# SAS_Connectors.net
KiCad netlist of a schematic drawn in Altium Designer
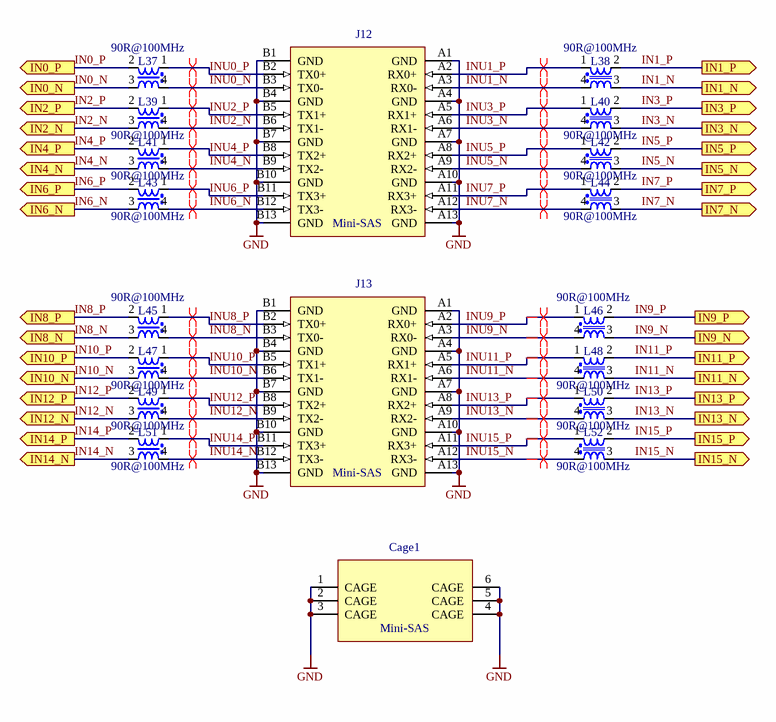
[diagram p0: SAS_Connectors.SchDoc]

(export (version "E")
  (design (tool "Eeschema 10.0.6"))
  (components
    (comp (ref "Cage1")
      (value "Mini-SAS")
      (footprint "TYCO_1888321-2")
      (description "Mini-SAS Cage (6Pins)")
      (fields
        (field (name "PART NUMBER") "TYCO_1888321-2")
        (field (name "MANUFACTURER") "TYCO ELECTRONICS")
        (field (name "AUTHOR") "CERN DEM BC")
      )
      (libsource (lib "Connectors") (part "Mini-SAS Cage (6Pins)"))
    )
    (comp (ref "J12")
      (value "Mini-SAS")
      (footprint "TYCO_1761987-7")
      (description "26 Position Mini-Sas Connector (Quad Small Form-Factor SFF-8088)")
      (fields
        (field (name "PART NUMBER") "TYCO_1761987-7")
        (field (name "MANUFACTURER") "TYCO ELECTRONICS")
        (field (name "AUTHOR") "CERN DEM MR")
      )
      (libsource (lib "Connectors") (part "Mini-SAS"))
    )
    (comp (ref "J13")
      (value "Mini-SAS")
      (footprint "TYCO_1761987-7")
      (description "26 Position Mini-Sas Connector (Quad Small Form-Factor SFF-8088)")
      (fields
        (field (name "PART NUMBER") "TYCO_1761987-7")
        (field (name "MANUFACTURER") "TYCO ELECTRONICS")
        (field (name "AUTHOR") "CERN DEM MR")
      )
      (libsource (lib "Connectors") (part "Mini-SAS"))
    )
    (comp (ref "L37")
      (value "90R@100MHz")
      (footprint "IND_MURATA_DLW21S")
      (description "Inductor Common Mode")
      (fields
        (field (name "PART NUMBER") "IND_MURATA_DLW21SN900SQ2L")
        (field (name "POWER") "330mA")
        (field (name "AUTHOR") "CERN DEM JLC")
      )
      (libsource (lib "Inductors & Transformers") (part "Inductor Common Mode 1Dot-2 4Dot-3"))
    )
    (comp (ref "L38")
      (value "90R@100MHz")
      (footprint "IND_MURATA_DLW21S")
      (description "Inductor Common Mode")
      (fields
        (field (name "PART NUMBER") "IND_MURATA_DLW21SN900SQ2L")
        (field (name "POWER") "330mA")
        (field (name "AUTHOR") "CERN DEM JLC")
      )
      (libsource (lib "") (part "Inductor Common Mode 1Dot-2 4Dot-3_1"))
    )
    (comp (ref "L39")
      (value "90R@100MHz")
      (footprint "IND_MURATA_DLW21S")
      (description "Inductor Common Mode")
      (fields
        (field (name "PART NUMBER") "IND_MURATA_DLW21SN900SQ2L")
        (field (name "POWER") "330mA")
        (field (name "AUTHOR") "CERN DEM JLC")
      )
      (libsource (lib "Inductors & Transformers") (part "Inductor Common Mode 1Dot-2 4Dot-3"))
    )
    (comp (ref "L40")
      (value "90R@100MHz")
      (footprint "IND_MURATA_DLW21S")
      (description "Inductor Common Mode")
      (fields
        (field (name "PART NUMBER") "IND_MURATA_DLW21SN900SQ2L")
        (field (name "POWER") "330mA")
        (field (name "AUTHOR") "CERN DEM JLC")
      )
      (libsource (lib "") (part "Inductor Common Mode 1Dot-2 4Dot-3_1"))
    )
    (comp (ref "L41")
      (value "90R@100MHz")
      (footprint "IND_MURATA_DLW21S")
      (description "Inductor Common Mode")
      (fields
        (field (name "PART NUMBER") "IND_MURATA_DLW21SN900SQ2L")
        (field (name "POWER") "330mA")
        (field (name "AUTHOR") "CERN DEM JLC")
      )
      (libsource (lib "Inductors & Transformers") (part "Inductor Common Mode 1Dot-2 4Dot-3"))
    )
    (comp (ref "L42")
      (value "90R@100MHz")
      (footprint "IND_MURATA_DLW21S")
      (description "Inductor Common Mode")
      (fields
        (field (name "PART NUMBER") "IND_MURATA_DLW21SN900SQ2L")
        (field (name "POWER") "330mA")
        (field (name "AUTHOR") "CERN DEM JLC")
      )
      (libsource (lib "") (part "Inductor Common Mode 1Dot-2 4Dot-3_1"))
    )
    (comp (ref "L43")
      (value "90R@100MHz")
      (footprint "IND_MURATA_DLW21S")
      (description "Inductor Common Mode")
      (fields
        (field (name "PART NUMBER") "IND_MURATA_DLW21SN900SQ2L")
        (field (name "POWER") "330mA")
        (field (name "AUTHOR") "CERN DEM JLC")
      )
      (libsource (lib "Inductors & Transformers") (part "Inductor Common Mode 1Dot-2 4Dot-3"))
    )
    (comp (ref "L44")
      (value "90R@100MHz")
      (footprint "IND_MURATA_DLW21S")
      (description "Inductor Common Mode")
      (fields
        (field (name "PART NUMBER") "IND_MURATA_DLW21SN900SQ2L")
        (field (name "POWER") "330mA")
        (field (name "AUTHOR") "CERN DEM JLC")
      )
      (libsource (lib "") (part "Inductor Common Mode 1Dot-2 4Dot-3_1"))
    )
    (comp (ref "L45")
      (value "90R@100MHz")
      (footprint "IND_MURATA_DLW21S")
      (description "Inductor Common Mode")
      (fields
        (field (name "PART NUMBER") "IND_MURATA_DLW21SN900SQ2L")
        (field (name "POWER") "330mA")
        (field (name "AUTHOR") "CERN DEM JLC")
      )
      (libsource (lib "Inductors & Transformers") (part "Inductor Common Mode 1Dot-2 4Dot-3"))
    )
    (comp (ref "L46")
      (value "90R@100MHz")
      (footprint "IND_MURATA_DLW21S")
      (description "Inductor Common Mode")
      (fields
        (field (name "PART NUMBER") "IND_MURATA_DLW21SN900SQ2L")
        (field (name "POWER") "330mA")
        (field (name "AUTHOR") "CERN DEM JLC")
      )
      (libsource (lib "") (part "Inductor Common Mode 1Dot-2 4Dot-3_1"))
    )
    (comp (ref "L47")
      (value "90R@100MHz")
      (footprint "IND_MURATA_DLW21S")
      (description "Inductor Common Mode")
      (fields
        (field (name "PART NUMBER") "IND_MURATA_DLW21SN900SQ2L")
        (field (name "POWER") "330mA")
        (field (name "AUTHOR") "CERN DEM JLC")
      )
      (libsource (lib "Inductors & Transformers") (part "Inductor Common Mode 1Dot-2 4Dot-3"))
    )
    (comp (ref "L48")
      (value "90R@100MHz")
      (footprint "IND_MURATA_DLW21S")
      (description "Inductor Common Mode")
      (fields
        (field (name "PART NUMBER") "IND_MURATA_DLW21SN900SQ2L")
        (field (name "POWER") "330mA")
        (field (name "AUTHOR") "CERN DEM JLC")
      )
      (libsource (lib "") (part "Inductor Common Mode 1Dot-2 4Dot-3_1"))
    )
    (comp (ref "L49")
      (value "90R@100MHz")
      (footprint "IND_MURATA_DLW21S")
      (description "Inductor Common Mode")
      (fields
        (field (name "PART NUMBER") "IND_MURATA_DLW21SN900SQ2L")
        (field (name "POWER") "330mA")
        (field (name "AUTHOR") "CERN DEM JLC")
      )
      (libsource (lib "Inductors & Transformers") (part "Inductor Common Mode 1Dot-2 4Dot-3"))
    )
    (comp (ref "L50")
      (value "90R@100MHz")
      (footprint "IND_MURATA_DLW21S")
      (description "Inductor Common Mode")
      (fields
        (field (name "PART NUMBER") "IND_MURATA_DLW21SN900SQ2L")
        (field (name "POWER") "330mA")
        (field (name "AUTHOR") "CERN DEM JLC")
      )
      (libsource (lib "") (part "Inductor Common Mode 1Dot-2 4Dot-3_1"))
    )
    (comp (ref "L51")
      (value "90R@100MHz")
      (footprint "IND_MURATA_DLW21S")
      (description "Inductor Common Mode")
      (fields
        (field (name "PART NUMBER") "IND_MURATA_DLW21SN900SQ2L")
        (field (name "POWER") "330mA")
        (field (name "AUTHOR") "CERN DEM JLC")
      )
      (libsource (lib "Inductors & Transformers") (part "Inductor Common Mode 1Dot-2 4Dot-3"))
    )
    (comp (ref "L52")
      (value "90R@100MHz")
      (footprint "IND_MURATA_DLW21S")
      (description "Inductor Common Mode")
      (fields
        (field (name "PART NUMBER") "IND_MURATA_DLW21SN900SQ2L")
        (field (name "POWER") "330mA")
        (field (name "AUTHOR") "CERN DEM JLC")
      )
      (libsource (lib "") (part "Inductor Common Mode 1Dot-2 4Dot-3_1"))
    )
  )
  (nets
    (net (code "1") (name "/IN0_N") (class "Default")
      (node (ref "L37") (pin "3") (pinfunction "3_3") (pintype "passive"))
    )
    (net (code "2") (name "/IN0_P") (class "Default")
      (node (ref "L37") (pin "2") (pinfunction "2_2") (pintype "passive"))
    )
    (net (code "3") (name "/IN1_N") (class "Default")
      (node (ref "L38") (pin "3") (pinfunction "3_3") (pintype "passive"))
    )
    (net (code "4") (name "/IN1_P") (class "Default")
      (node (ref "L38") (pin "2") (pinfunction "2_2") (pintype "passive"))
    )
    (net (code "5") (name "/IN2_N") (class "Default")
      (node (ref "L39") (pin "3") (pinfunction "3_3") (pintype "passive"))
    )
    (net (code "6") (name "/IN2_P") (class "Default")
      (node (ref "L39") (pin "2") (pinfunction "2_2") (pintype "passive"))
    )
    (net (code "7") (name "/IN3_N") (class "Default")
      (node (ref "L40") (pin "3") (pinfunction "3_3") (pintype "passive"))
    )
    (net (code "8") (name "/IN3_P") (class "Default")
      (node (ref "L40") (pin "2") (pinfunction "2_2") (pintype "passive"))
    )
    (net (code "9") (name "/IN4_N") (class "Default")
      (node (ref "L41") (pin "3") (pinfunction "3_3") (pintype "passive"))
    )
    (net (code "10") (name "/IN4_P") (class "Default")
      (node (ref "L41") (pin "2") (pinfunction "2_2") (pintype "passive"))
    )
    (net (code "11") (name "/IN5_N") (class "Default")
      (node (ref "L42") (pin "3") (pinfunction "3_3") (pintype "passive"))
    )
    (net (code "12") (name "/IN5_P") (class "Default")
      (node (ref "L42") (pin "2") (pinfunction "2_2") (pintype "passive"))
    )
    (net (code "13") (name "/IN6_N") (class "Default")
      (node (ref "L43") (pin "3") (pinfunction "3_3") (pintype "passive"))
    )
    (net (code "14") (name "/IN6_P") (class "Default")
      (node (ref "L43") (pin "2") (pinfunction "2_2") (pintype "passive"))
    )
    (net (code "15") (name "/IN7_N") (class "Default")
      (node (ref "L44") (pin "3") (pinfunction "3_3") (pintype "passive"))
    )
    (net (code "16") (name "/IN7_P") (class "Default")
      (node (ref "L44") (pin "2") (pinfunction "2_2") (pintype "passive"))
    )
    (net (code "17") (name "/IN8_N") (class "Default")
      (node (ref "L45") (pin "3") (pinfunction "3_3") (pintype "passive"))
    )
    (net (code "18") (name "/IN8_P") (class "Default")
      (node (ref "L45") (pin "2") (pinfunction "2_2") (pintype "passive"))
    )
    (net (code "19") (name "/IN9_N") (class "Default")
      (node (ref "L46") (pin "3") (pinfunction "3_3") (pintype "passive"))
    )
    (net (code "20") (name "/IN9_P") (class "Default")
      (node (ref "L46") (pin "2") (pinfunction "2_2") (pintype "passive"))
    )
    (net (code "21") (name "/IN10_N") (class "Default")
      (node (ref "L47") (pin "3") (pinfunction "3_3") (pintype "passive"))
    )
    (net (code "22") (name "/IN10_P") (class "Default")
      (node (ref "L47") (pin "2") (pinfunction "2_2") (pintype "passive"))
    )
    (net (code "23") (name "/IN11_N") (class "Default")
      (node (ref "L48") (pin "3") (pinfunction "3_3") (pintype "passive"))
    )
    (net (code "24") (name "/IN11_P") (class "Default")
      (node (ref "L48") (pin "2") (pinfunction "2_2") (pintype "passive"))
    )
    (net (code "25") (name "/IN12_N") (class "Default")
      (node (ref "L49") (pin "3") (pinfunction "3_3") (pintype "passive"))
    )
    (net (code "26") (name "/IN12_P") (class "Default")
      (node (ref "L49") (pin "2") (pinfunction "2_2") (pintype "passive"))
    )
    (net (code "27") (name "/IN13_N") (class "Default")
      (node (ref "L50") (pin "3") (pinfunction "3_3") (pintype "passive"))
    )
    (net (code "28") (name "/IN13_P") (class "Default")
      (node (ref "L50") (pin "2") (pinfunction "2_2") (pintype "passive"))
    )
    (net (code "29") (name "/IN14_N") (class "Default")
      (node (ref "L51") (pin "3") (pinfunction "3_3") (pintype "passive"))
    )
    (net (code "30") (name "/IN14_P") (class "Default")
      (node (ref "L51") (pin "2") (pinfunction "2_2") (pintype "passive"))
    )
    (net (code "31") (name "/IN15_N") (class "Default")
      (node (ref "L52") (pin "3") (pinfunction "3_3") (pintype "passive"))
    )
    (net (code "32") (name "/IN15_P") (class "Default")
      (node (ref "L52") (pin "2") (pinfunction "2_2") (pintype "passive"))
    )
    (net (code "33") (name "/INU0_N") (class "Default")
      (node (ref "J12") (pin "B3") (pinfunction "TX0-_B3") (pintype "input"))
      (node (ref "L37") (pin "4") (pinfunction "4_4") (pintype "passive"))
    )
    (net (code "34") (name "/INU0_P") (class "Default")
      (node (ref "J12") (pin "B2") (pinfunction "TX0+_B2") (pintype "input"))
      (node (ref "L37") (pin "1") (pinfunction "1_1") (pintype "passive"))
    )
    (net (code "35") (name "/INU1_N") (class "Default")
      (node (ref "J12") (pin "A3") (pinfunction "RX0-_A3") (pintype "input"))
      (node (ref "L38") (pin "4") (pinfunction "4_4") (pintype "passive"))
    )
    (net (code "36") (name "/INU1_P") (class "Default")
      (node (ref "J12") (pin "A2") (pinfunction "RX0+_A2") (pintype "input"))
      (node (ref "L38") (pin "1") (pinfunction "1_1") (pintype "passive"))
    )
    (net (code "37") (name "/INU2_N") (class "Default")
      (node (ref "J12") (pin "B6") (pinfunction "TX1-_B6") (pintype "input"))
      (node (ref "L39") (pin "4") (pinfunction "4_4") (pintype "passive"))
    )
    (net (code "38") (name "/INU2_P") (class "Default")
      (node (ref "J12") (pin "B5") (pinfunction "TX1+_B5") (pintype "input"))
      (node (ref "L39") (pin "1") (pinfunction "1_1") (pintype "passive"))
    )
    (net (code "39") (name "/INU3_N") (class "Default")
      (node (ref "J12") (pin "A6") (pinfunction "RX1-_A6") (pintype "input"))
      (node (ref "L40") (pin "4") (pinfunction "4_4") (pintype "passive"))
    )
    (net (code "40") (name "/INU3_P") (class "Default")
      (node (ref "J12") (pin "A5") (pinfunction "RX1+_A5") (pintype "input"))
      (node (ref "L40") (pin "1") (pinfunction "1_1") (pintype "passive"))
    )
    (net (code "41") (name "/INU4_N") (class "Default")
      (node (ref "J12") (pin "B9") (pinfunction "TX2-_B9") (pintype "input"))
      (node (ref "L41") (pin "4") (pinfunction "4_4") (pintype "passive"))
    )
    (net (code "42") (name "/INU4_P") (class "Default")
      (node (ref "J12") (pin "B8") (pinfunction "TX2+_B8") (pintype "input"))
      (node (ref "L41") (pin "1") (pinfunction "1_1") (pintype "passive"))
    )
    (net (code "43") (name "/INU5_N") (class "Default")
      (node (ref "J12") (pin "A9") (pinfunction "RX2-_A9") (pintype "input"))
      (node (ref "L42") (pin "4") (pinfunction "4_4") (pintype "passive"))
    )
    (net (code "44") (name "/INU5_P") (class "Default")
      (node (ref "J12") (pin "A8") (pinfunction "RX2+_A8") (pintype "input"))
      (node (ref "L42") (pin "1") (pinfunction "1_1") (pintype "passive"))
    )
    (net (code "45") (name "/INU6_N") (class "Default")
      (node (ref "J12") (pin "B12") (pinfunction "TX3-_B12") (pintype "input"))
      (node (ref "L43") (pin "4") (pinfunction "4_4") (pintype "passive"))
    )
    (net (code "46") (name "/INU6_P") (class "Default")
      (node (ref "J12") (pin "B11") (pinfunction "TX3+_B11") (pintype "input"))
      (node (ref "L43") (pin "1") (pinfunction "1_1") (pintype "passive"))
    )
    (net (code "47") (name "/INU7_N") (class "Default")
      (node (ref "J12") (pin "A12") (pinfunction "RX3-_A12") (pintype "input"))
      (node (ref "L44") (pin "4") (pinfunction "4_4") (pintype "passive"))
    )
    (net (code "48") (name "/INU7_P") (class "Default")
      (node (ref "J12") (pin "A11") (pinfunction "RX3+_A11") (pintype "input"))
      (node (ref "L44") (pin "1") (pinfunction "1_1") (pintype "passive"))
    )
    (net (code "49") (name "/INU8_N") (class "Default")
      (node (ref "J13") (pin "B3") (pinfunction "TX0-_B3") (pintype "input"))
      (node (ref "L45") (pin "4") (pinfunction "4_4") (pintype "passive"))
    )
    (net (code "50") (name "/INU8_P") (class "Default")
      (node (ref "J13") (pin "B2") (pinfunction "TX0+_B2") (pintype "input"))
      (node (ref "L45") (pin "1") (pinfunction "1_1") (pintype "passive"))
    )
    (net (code "51") (name "/INU9_N") (class "Default")
      (node (ref "J13") (pin "A3") (pinfunction "RX0-_A3") (pintype "input"))
      (node (ref "L46") (pin "4") (pinfunction "4_4") (pintype "passive"))
    )
    (net (code "52") (name "/INU9_P") (class "Default")
      (node (ref "J13") (pin "A2") (pinfunction "RX0+_A2") (pintype "input"))
      (node (ref "L46") (pin "1") (pinfunction "1_1") (pintype "passive"))
    )
    (net (code "53") (name "/INU10_N") (class "Default")
      (node (ref "J13") (pin "B6") (pinfunction "TX1-_B6") (pintype "input"))
      (node (ref "L47") (pin "4") (pinfunction "4_4") (pintype "passive"))
    )
    (net (code "54") (name "/INU10_P") (class "Default")
      (node (ref "J13") (pin "B5") (pinfunction "TX1+_B5") (pintype "input"))
      (node (ref "L47") (pin "1") (pinfunction "1_1") (pintype "passive"))
    )
    (net (code "55") (name "/INU11_N") (class "Default")
      (node (ref "J13") (pin "A6") (pinfunction "RX1-_A6") (pintype "input"))
      (node (ref "L48") (pin "4") (pinfunction "4_4") (pintype "passive"))
    )
    (net (code "56") (name "/INU11_P") (class "Default")
      (node (ref "J13") (pin "A5") (pinfunction "RX1+_A5") (pintype "input"))
      (node (ref "L48") (pin "1") (pinfunction "1_1") (pintype "passive"))
    )
    (net (code "57") (name "/INU12_N") (class "Default")
      (node (ref "J13") (pin "B9") (pinfunction "TX2-_B9") (pintype "input"))
      (node (ref "L49") (pin "4") (pinfunction "4_4") (pintype "passive"))
    )
    (net (code "58") (name "/INU12_P") (class "Default")
      (node (ref "J13") (pin "B8") (pinfunction "TX2+_B8") (pintype "input"))
      (node (ref "L49") (pin "1") (pinfunction "1_1") (pintype "passive"))
    )
    (net (code "59") (name "/INU13_N") (class "Default")
      (node (ref "J13") (pin "A9") (pinfunction "RX2-_A9") (pintype "input"))
      (node (ref "L50") (pin "4") (pinfunction "4_4") (pintype "passive"))
    )
    (net (code "60") (name "/INU13_P") (class "Default")
      (node (ref "J13") (pin "A8") (pinfunction "RX2+_A8") (pintype "input"))
      (node (ref "L50") (pin "1") (pinfunction "1_1") (pintype "passive"))
    )
    (net (code "61") (name "/INU14_N") (class "Default")
      (node (ref "J13") (pin "B12") (pinfunction "TX3-_B12") (pintype "input"))
      (node (ref "L51") (pin "4") (pinfunction "4_4") (pintype "passive"))
    )
    (net (code "62") (name "/INU14_P") (class "Default")
      (node (ref "J13") (pin "B11") (pinfunction "TX3+_B11") (pintype "input"))
      (node (ref "L51") (pin "1") (pinfunction "1_1") (pintype "passive"))
    )
    (net (code "63") (name "/INU15_N") (class "Default")
      (node (ref "J13") (pin "A12") (pinfunction "RX3-_A12") (pintype "input"))
      (node (ref "L52") (pin "4") (pinfunction "4_4") (pintype "passive"))
    )
    (net (code "64") (name "/INU15_P") (class "Default")
      (node (ref "J13") (pin "A11") (pinfunction "RX3+_A11") (pintype "input"))
      (node (ref "L52") (pin "1") (pinfunction "1_1") (pintype "passive"))
    )
    (net (code "65") (name "GND") (class "Default")
      (node (ref "Cage1") (pin "1") (pinfunction "CAGE_1") (pintype "power_in"))
      (node (ref "Cage1") (pin "2") (pinfunction "CAGE_2") (pintype "power_in"))
      (node (ref "Cage1") (pin "3") (pinfunction "CAGE_3") (pintype "power_in"))
      (node (ref "Cage1") (pin "4") (pinfunction "CAGE_4") (pintype "power_in"))
      (node (ref "Cage1") (pin "5") (pinfunction "CAGE_5") (pintype "power_in"))
      (node (ref "Cage1") (pin "6") (pinfunction "CAGE_6") (pintype "power_in"))
      (node (ref "J12") (pin "A1") (pinfunction "GND_A1") (pintype "power_in"))
      (node (ref "J12") (pin "A10") (pinfunction "GND_A10") (pintype "power_in"))
      (node (ref "J12") (pin "A13") (pinfunction "GND_A13") (pintype "power_in"))
      (node (ref "J12") (pin "A4") (pinfunction "GND_A4") (pintype "power_in"))
      (node (ref "J12") (pin "A7") (pinfunction "GND_A7") (pintype "power_in"))
      (node (ref "J12") (pin "B1") (pinfunction "GND_B1") (pintype "power_in"))
      (node (ref "J12") (pin "B10") (pinfunction "GND_B10") (pintype "power_in"))
      (node (ref "J12") (pin "B13") (pinfunction "GND_B13") (pintype "power_in"))
      (node (ref "J12") (pin "B4") (pinfunction "GND_B4") (pintype "power_in"))
      (node (ref "J12") (pin "B7") (pinfunction "GND_B7") (pintype "power_in"))
      (node (ref "J13") (pin "A1") (pinfunction "GND_A1") (pintype "power_in"))
      (node (ref "J13") (pin "A10") (pinfunction "GND_A10") (pintype "power_in"))
      (node (ref "J13") (pin "A13") (pinfunction "GND_A13") (pintype "power_in"))
      (node (ref "J13") (pin "A4") (pinfunction "GND_A4") (pintype "power_in"))
      (node (ref "J13") (pin "A7") (pinfunction "GND_A7") (pintype "power_in"))
      (node (ref "J13") (pin "B1") (pinfunction "GND_B1") (pintype "power_in"))
      (node (ref "J13") (pin "B10") (pinfunction "GND_B10") (pintype "power_in"))
      (node (ref "J13") (pin "B13") (pinfunction "GND_B13") (pintype "power_in"))
      (node (ref "J13") (pin "B4") (pinfunction "GND_B4") (pintype "power_in"))
      (node (ref "J13") (pin "B7") (pinfunction "GND_B7") (pintype "power_in"))
    )
  )
)
